# pertamina.net
KiCad netlist of a schematic drawn in EAGLE
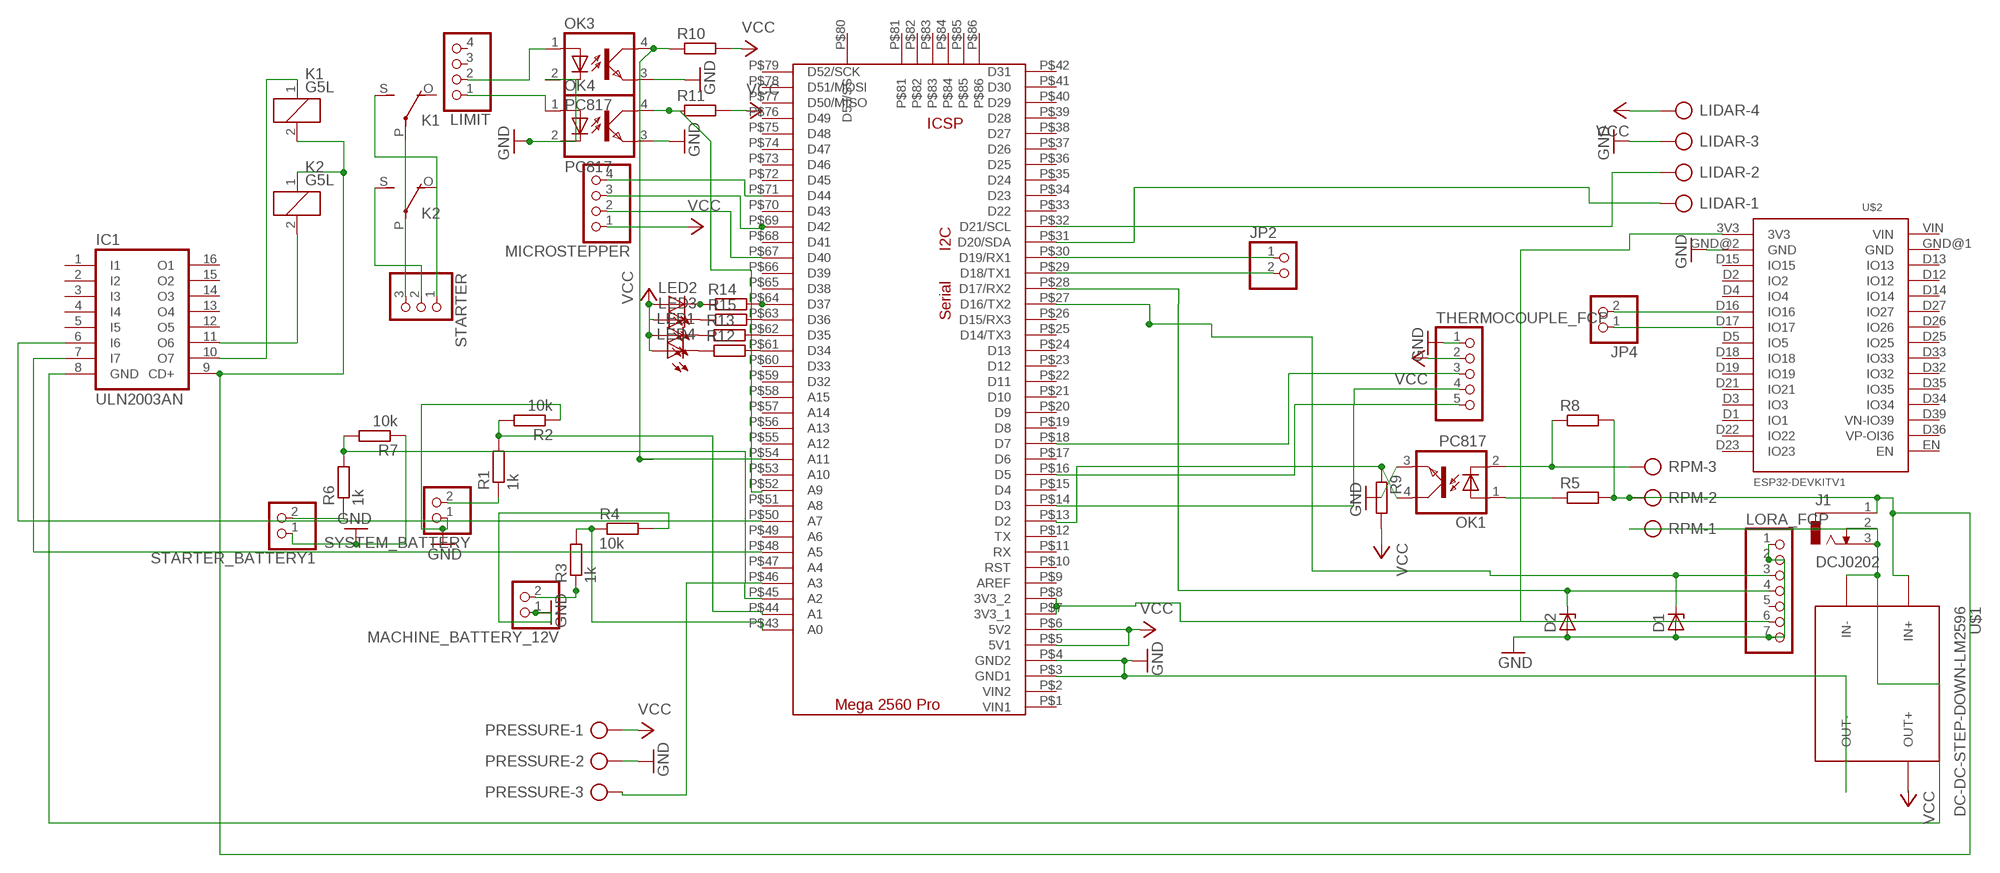
[diagram p0: schematic, sheet 1]

(export (version "E")
  (design (tool "Eeschema 10.0.6"))
  (components
    (comp (ref "D1")
      (value "ZENER-DIODEDO35Z10")
      (footprint "eagle-import:DO35Z10")
      (libsource (lib "eagle-import") (part "ZENER-DIODEDO35Z10"))
    )
    (comp (ref "D2")
      (value "ZENER-DIODEDO35Z10")
      (footprint "eagle-import:DO35Z10")
      (libsource (lib "eagle-import") (part "ZENER-DIODEDO35Z10"))
    )
    (comp (ref "IC1")
      (value "ULN2003AN")
      (footprint "eagle-import:DIL16")
      (libsource (lib "eagle-import") (part "ULN2003AN"))
    )
    (comp (ref "J1")
      (value "DCJ0202")
      (footprint "eagle-import:DCJ0202")
      (libsource (lib "eagle-import") (part "DCJ0202"))
    )
    (comp (ref "JP2")
      (value "PINHD-1X2")
      (footprint "eagle-import:1X02")
      (libsource (lib "eagle-import") (part "PINHD-1X2"))
    )
    (comp (ref "JP4")
      (value "PINHD-1X2")
      (footprint "eagle-import:1X02")
      (libsource (lib "eagle-import") (part "PINHD-1X2"))
    )
    (comp (ref "K1")
      (value "G5L")
      (footprint "eagle-import:G5LE")
      (libsource (lib "eagle-import") (part "G5L"))
    )
    (comp (ref "K2")
      (value "G5L")
      (footprint "eagle-import:G5LE")
      (libsource (lib "eagle-import") (part "G5L"))
    )
    (comp (ref "LED1")
      (value "LED5MM")
      (footprint "eagle-import:LED5MM")
      (libsource (lib "eagle-import") (part "LED5MM"))
    )
    (comp (ref "LED2")
      (value "LED5MM")
      (footprint "eagle-import:LED5MM")
      (libsource (lib "eagle-import") (part "LED5MM"))
    )
    (comp (ref "LED3")
      (value "LED5MM")
      (footprint "eagle-import:LED5MM")
      (libsource (lib "eagle-import") (part "LED5MM"))
    )
    (comp (ref "LED4")
      (value "LED5MM")
      (footprint "eagle-import:LED5MM")
      (libsource (lib "eagle-import") (part "LED5MM"))
    )
    (comp (ref "LIDAR")
      (value "AK300/4")
      (footprint "eagle-import:AK300_4")
      (libsource (lib "eagle-import") (part "AK300/4"))
    )
    (comp (ref "LIMIT")
      (value "PINHD-1X4")
      (footprint "eagle-import:1X04")
      (libsource (lib "eagle-import") (part "PINHD-1X4"))
    )
    (comp (ref "LORA_FCP")
      (value "PINHD-1X7")
      (footprint "eagle-import:1X07")
      (libsource (lib "eagle-import") (part "PINHD-1X7"))
    )
    (comp (ref "MACHINE_BATTERY_12V")
      (value "PINHD-1X2")
      (footprint "eagle-import:1X02")
      (libsource (lib "eagle-import") (part "PINHD-1X2"))
    )
    (comp (ref "MICROSTEPPER")
      (value "PINHD-1X4")
      (footprint "eagle-import:1X04")
      (libsource (lib "eagle-import") (part "PINHD-1X4"))
    )
    (comp (ref "OK1")
      (value "PC817")
      (footprint "eagle-import:DIL04")
      (fields (field (name "MPN") "PC817X4J000F"))
      (libsource (lib "eagle-import") (part "PC817"))
    )
    (comp (ref "OK3")
      (value "PC817")
      (footprint "eagle-import:DIL04")
      (fields (field (name "MPN") "PC817X4J000F"))
      (libsource (lib "eagle-import") (part "PC817"))
    )
    (comp (ref "OK4")
      (value "PC817")
      (footprint "eagle-import:DIL04")
      (fields (field (name "MPN") "PC817X4J000F"))
      (libsource (lib "eagle-import") (part "PC817"))
    )
    (comp (ref "PRESSURE")
      (value "AK300/3")
      (footprint "eagle-import:AK300_3")
      (libsource (lib "eagle-import") (part "AK300/3"))
    )
    (comp (ref "R1")
      (value "1k")
      (footprint "eagle-import:0204_7")
      (libsource (lib "eagle-import") (part "R-EU_0204/7"))
    )
    (comp (ref "R2")
      (value "10k")
      (footprint "eagle-import:0204_7")
      (libsource (lib "eagle-import") (part "R-EU_0204/7"))
    )
    (comp (ref "R3")
      (value "1k")
      (footprint "eagle-import:0204_7")
      (libsource (lib "eagle-import") (part "R-EU_0204/7"))
    )
    (comp (ref "R4")
      (value "10k")
      (footprint "eagle-import:0204_7")
      (libsource (lib "eagle-import") (part "R-EU_0204/7"))
    )
    (comp (ref "R5")
      (value "R-EU_0204/7")
      (footprint "eagle-import:0204_7")
      (libsource (lib "eagle-import") (part "R-EU_0204/7"))
    )
    (comp (ref "R6")
      (value "1k")
      (footprint "eagle-import:0204_7")
      (libsource (lib "eagle-import") (part "R-EU_0204/7"))
    )
    (comp (ref "R7")
      (value "10k")
      (footprint "eagle-import:0204_7")
      (libsource (lib "eagle-import") (part "R-EU_0204/7"))
    )
    (comp (ref "R8")
      (value "R-EU_0204/7")
      (footprint "eagle-import:0204_7")
      (libsource (lib "eagle-import") (part "R-EU_0204/7"))
    )
    (comp (ref "R9")
      (value "R-EU_0204/7")
      (footprint "eagle-import:0204_7")
      (libsource (lib "eagle-import") (part "R-EU_0204/7"))
    )
    (comp (ref "R10")
      (value "R-EU_0204/7")
      (footprint "eagle-import:0204_7")
      (libsource (lib "eagle-import") (part "R-EU_0204/7"))
    )
    (comp (ref "R11")
      (value "R-EU_0204/7")
      (footprint "eagle-import:0204_7")
      (libsource (lib "eagle-import") (part "R-EU_0204/7"))
    )
    (comp (ref "R12")
      (value "R-EU_0204/7")
      (footprint "eagle-import:0204_7")
      (libsource (lib "eagle-import") (part "resistor_R-EU_0204/7"))
    )
    (comp (ref "R13")
      (value "R-EU_0204/7")
      (footprint "eagle-import:0204_7")
      (libsource (lib "eagle-import") (part "resistor_R-EU_0204/7"))
    )
    (comp (ref "R14")
      (value "R-EU_0204/7")
      (footprint "eagle-import:0204_7")
      (libsource (lib "eagle-import") (part "resistor_R-EU_0204/7"))
    )
    (comp (ref "R15")
      (value "R-EU_0204/7")
      (footprint "eagle-import:0204_7")
      (libsource (lib "eagle-import") (part "resistor_R-EU_0204/7"))
    )
    (comp (ref "RPM")
      (value "AK300/3")
      (footprint "eagle-import:AK300_3")
      (libsource (lib "eagle-import") (part "AK300/3"))
    )
    (comp (ref "STARTER")
      (value "PINHD-1X3")
      (footprint "eagle-import:1X03")
      (libsource (lib "eagle-import") (part "PINHD-1X3"))
    )
    (comp (ref "STARTER_BATTERY1")
      (value "PINHD-1X2")
      (footprint "eagle-import:1X02")
      (libsource (lib "eagle-import") (part "PINHD-1X2"))
    )
    (comp (ref "SYSTEM_BATTERY")
      (value "PINHD-1X2")
      (footprint "eagle-import:1X02")
      (libsource (lib "eagle-import") (part "PINHD-1X2"))
    )
    (comp (ref "THERMOCOUPLE_FCP")
      (value "PINHD-1X5")
      (footprint "eagle-import:1X05")
      (libsource (lib "eagle-import") (part "PINHD-1X5"))
    )
    (comp (ref "U$1")
      (value "DC-DC-STEP-DOWN-LM2596")
      (footprint "eagle-import:DC-DC-STEP-DOWN-LM2596")
      (libsource (lib "eagle-import") (part "DC-DC-STEP-DOWN-LM2596"))
    )
    (comp (ref "U$2")
      (value "ESP32DEVKITV1")
      (footprint "eagle-import:ESP32-DEVKITV1")
      (libsource (lib "eagle-import") (part "ESP32DEVKITV1"))
    )
    (comp (ref "U$3")
      (value "MEGAPROMINI")
      (footprint "eagle-import:MEGAPROMINI")
      (libsource (lib "eagle-import") (part "MEGAPROMINI"))
    )
  )
  (nets
    (net (code "1") (name "GND") (class "Default")
      (node (ref "D1") (pin "A") (pinfunction "A_A") (pintype "passive"))
      (node (ref "D2") (pin "A") (pinfunction "A_A") (pintype "passive"))
      (node (ref "LIDAR") (pin "3") (pinfunction "KL_3") (pintype "passive"))
      (node (ref "LORA_FCP") (pin "1") (pinfunction "1_1") (pintype "passive"))
      (node (ref "LORA_FCP") (pin "2") (pinfunction "2_2") (pintype "passive"))
      (node (ref "LORA_FCP") (pin "7") (pinfunction "7_7") (pintype "passive"))
      (node (ref "MACHINE_BATTERY_12V") (pin "1") (pinfunction "1_1") (pintype "passive"))
      (node (ref "OK1") (pin "3") (pinfunction "EMIT_3") (pintype "passive"))
      (node (ref "OK3") (pin "2") (pinfunction "C_2") (pintype "passive"))
      (node (ref "OK3") (pin "3") (pinfunction "EMIT_3") (pintype "passive"))
      (node (ref "OK4") (pin "2") (pinfunction "C_2") (pintype "passive"))
      (node (ref "OK4") (pin "3") (pinfunction "EMIT_3") (pintype "passive"))
      (node (ref "PRESSURE") (pin "2") (pinfunction "KL_2") (pintype "passive"))
      (node (ref "R2") (pin "1") (pinfunction "1_1") (pintype "passive"))
      (node (ref "R4") (pin "2") (pinfunction "2_2") (pintype "passive"))
      (node (ref "R7") (pin "1") (pinfunction "1_1") (pintype "passive"))
      (node (ref "STARTER_BATTERY1") (pin "1") (pinfunction "1_1") (pintype "passive"))
      (node (ref "SYSTEM_BATTERY") (pin "1") (pinfunction "1_1") (pintype "passive"))
      (node (ref "THERMOCOUPLE_FCP") (pin "1") (pinfunction "1_1") (pintype "passive"))
      (node (ref "U$1") (pin "OUT-") (pinfunction "OUT-_OUT-") (pintype "bidirectional"))
      (node (ref "U$2") (pin "GND@2") (pinfunction "GND_GND@2") (pintype "bidirectional"))
      (node (ref "U$3") (pin "P$3") (pinfunction "GND1_P$3") (pintype "bidirectional"))
      (node (ref "U$3") (pin "P$4") (pinfunction "GND2_P$4") (pintype "bidirectional"))
    )
    (net (code "2") (name "Net-(IC1-CD+)") (class "Default")
      (node (ref "IC1") (pin "9") (pinfunction "CD+_9") (pintype "passive"))
      (node (ref "J1") (pin "1") (pinfunction "1_1") (pintype "passive"))
      (node (ref "K1") (pin "2") (pinfunction "2_2") (pintype "passive"))
      (node (ref "K2") (pin "1") (pinfunction "1_1") (pintype "passive"))
      (node (ref "R5") (pin "2") (pinfunction "2_2") (pintype "passive"))
      (node (ref "R8") (pin "2") (pinfunction "2_2") (pintype "passive"))
      (node (ref "RPM") (pin "2") (pinfunction "KL_2") (pintype "passive"))
      (node (ref "U$1") (pin "IN+") (pinfunction "IN+_IN+") (pintype "bidirectional"))
    )
    (net (code "3") (name "Net-(IC1-GND)") (class "Default")
      (node (ref "IC1") (pin "8") (pinfunction "GND_8") (pintype "power_in"))
      (node (ref "J1") (pin "2") (pinfunction "2_2") (pintype "passive"))
      (node (ref "J1") (pin "3") (pinfunction "3_3") (pintype "passive"))
      (node (ref "RPM") (pin "1") (pinfunction "KL_1") (pintype "passive"))
      (node (ref "U$1") (pin "IN-") (pinfunction "IN-_IN-") (pintype "bidirectional"))
    )
    (net (code "4") (name "Net-(IC1-I6)") (class "Default")
      (node (ref "IC1") (pin "6") (pinfunction "I6_6") (pintype "input"))
      (node (ref "U$3") (pin "P$50") (pinfunction "A7_P$50") (pintype "bidirectional"))
    )
    (net (code "5") (name "Net-(IC1-I7)") (class "Default")
      (node (ref "IC1") (pin "7") (pinfunction "I7_7") (pintype "input"))
      (node (ref "U$3") (pin "P$48") (pinfunction "A5_P$48") (pintype "bidirectional"))
    )
    (net (code "6") (name "Net-(IC1-O6)") (class "Default")
      (node (ref "IC1") (pin "11") (pinfunction "O6_11") (pintype "open_collector"))
      (node (ref "K2") (pin "2") (pinfunction "2_2") (pintype "passive"))
    )
    (net (code "7") (name "Net-(IC1-O7)") (class "Default")
      (node (ref "IC1") (pin "10") (pinfunction "O7_10") (pintype "open_collector"))
      (node (ref "K1") (pin "1") (pinfunction "1_1") (pintype "passive"))
    )
    (net (code "8") (name "Net-(K1-PadP)") (class "Default")
      (node (ref "K1") (pin "P") (pinfunction "P_P") (pintype "passive"))
      (node (ref "K2") (pin "P") (pinfunction "P_P") (pintype "passive"))
      (node (ref "STARTER") (pin "3") (pinfunction "3_3") (pintype "passive"))
    )
    (net (code "9") (name "Net-(K1-PadS)") (class "Default")
      (node (ref "K1") (pin "S") (pinfunction "S_S") (pintype "passive"))
      (node (ref "STARTER") (pin "1") (pinfunction "1_1") (pintype "passive"))
    )
    (net (code "10") (name "Net-(K2-PadS)") (class "Default")
      (node (ref "K2") (pin "S") (pinfunction "S_S") (pintype "passive"))
      (node (ref "STARTER") (pin "2") (pinfunction "2_2") (pintype "passive"))
    )
    (net (code "11") (name "Net-(LED1-C)") (class "Default")
      (node (ref "LED1") (pin "K") (pinfunction "C_K") (pintype "passive"))
      (node (ref "R13") (pin "1") (pinfunction "1_1") (pintype "passive"))
    )
    (net (code "12") (name "Net-(LED2-C)") (class "Default")
      (node (ref "LED2") (pin "K") (pinfunction "C_K") (pintype "passive"))
      (node (ref "R14") (pin "1") (pinfunction "1_1") (pintype "passive"))
    )
    (net (code "13") (name "Net-(LED3-C)") (class "Default")
      (node (ref "LED3") (pin "K") (pinfunction "C_K") (pintype "passive"))
      (node (ref "R15") (pin "1") (pinfunction "1_1") (pintype "passive"))
    )
    (net (code "14") (name "Net-(LED4-C)") (class "Default")
      (node (ref "LED4") (pin "K") (pinfunction "C_K") (pintype "passive"))
      (node (ref "R12") (pin "1") (pinfunction "1_1") (pintype "passive"))
    )
    (net (code "15") (name "Net-(LIDARA-KL)") (class "Default")
      (node (ref "LIDAR") (pin "1") (pinfunction "KL_1") (pintype "passive"))
      (node (ref "U$3") (pin "P$31") (pinfunction "D20/SDA_P$31") (pintype "bidirectional"))
    )
    (net (code "16") (name "Net-(LIDARB-KL)") (class "Default")
      (node (ref "LIDAR") (pin "2") (pinfunction "KL_2") (pintype "passive"))
      (node (ref "U$3") (pin "P$32") (pinfunction "D21/SCL_P$32") (pintype "bidirectional"))
    )
    (net (code "17") (name "Net-(MACHINE_BATTERY_12V-Pad2)") (class "Default")
      (node (ref "MACHINE_BATTERY_12V") (pin "2") (pinfunction "2_2") (pintype "passive"))
      (node (ref "R3") (pin "1") (pinfunction "1_1") (pintype "passive"))
    )
    (net (code "18") (name "Net-(OK1-A)") (class "Default")
      (node (ref "OK1") (pin "1") (pinfunction "A_1") (pintype "passive"))
      (node (ref "R5") (pin "1") (pinfunction "1_1") (pintype "passive"))
    )
    (net (code "19") (name "Net-(OK1-C)") (class "Default")
      (node (ref "OK1") (pin "2") (pinfunction "C_2") (pintype "passive"))
      (node (ref "R8") (pin "1") (pinfunction "1_1") (pintype "passive"))
      (node (ref "RPM") (pin "3") (pinfunction "KL_3") (pintype "passive"))
    )
    (net (code "20") (name "Net-(OK1-COL)") (class "Default")
      (node (ref "OK1") (pin "4") (pinfunction "COL_4") (pintype "passive"))
      (node (ref "R9") (pin "1") (pinfunction "1_1") (pintype "passive"))
      (node (ref "U$3") (pin "P$13") (pinfunction "D2_P$13") (pintype "bidirectional"))
    )
    (net (code "21") (name "Net-(OK3-A)") (class "Default")
      (node (ref "LIMIT") (pin "2") (pinfunction "2_2") (pintype "passive"))
      (node (ref "OK3") (pin "1") (pinfunction "A_1") (pintype "passive"))
    )
    (net (code "22") (name "Net-(OK3-COL)") (class "Default")
      (node (ref "OK3") (pin "4") (pinfunction "COL_4") (pintype "passive"))
      (node (ref "R10") (pin "1") (pinfunction "1_1") (pintype "passive"))
      (node (ref "U$3") (pin "P$54") (pinfunction "A11_P$54") (pintype "bidirectional"))
    )
    (net (code "23") (name "Net-(OK4-A)") (class "Default")
      (node (ref "LIMIT") (pin "1") (pinfunction "1_1") (pintype "passive"))
      (node (ref "OK4") (pin "1") (pinfunction "A_1") (pintype "passive"))
    )
    (net (code "24") (name "Net-(OK4-COL)") (class "Default")
      (node (ref "OK4") (pin "4") (pinfunction "COL_4") (pintype "passive"))
      (node (ref "R11") (pin "1") (pinfunction "1_1") (pintype "passive"))
      (node (ref "U$3") (pin "P$52") (pinfunction "A9_P$52") (pintype "bidirectional"))
    )
    (net (code "25") (name "Net-(PRESSUREC-KL)") (class "Default")
      (node (ref "PRESSURE") (pin "3") (pinfunction "KL_3") (pintype "passive"))
      (node (ref "U$3") (pin "P$46") (pinfunction "A3_P$46") (pintype "bidirectional"))
    )
    (net (code "26") (name "Net-(R1-Pad1)") (class "Default")
      (node (ref "R1") (pin "1") (pinfunction "1_1") (pintype "passive"))
      (node (ref "SYSTEM_BATTERY") (pin "2") (pinfunction "2_2") (pintype "passive"))
    )
    (net (code "27") (name "Net-(R6-Pad1)") (class "Default")
      (node (ref "R6") (pin "1") (pinfunction "1_1") (pintype "passive"))
      (node (ref "STARTER_BATTERY1") (pin "2") (pinfunction "2_2") (pintype "passive"))
    )
    (net (code "28") (name "Net-(U$2-IO16)") (class "Default")
      (node (ref "JP4") (pin "2") (pinfunction "2_2") (pintype "passive"))
      (node (ref "U$2") (pin "D16") (pinfunction "IO16_D16") (pintype "bidirectional"))
    )
    (net (code "29") (name "Net-(U$2-IO17)") (class "Default")
      (node (ref "JP4") (pin "1") (pinfunction "1_1") (pintype "passive"))
      (node (ref "U$2") (pin "D17") (pinfunction "IO17_D17") (pintype "bidirectional"))
    )
    (net (code "30") (name "Net-(U$3-3V3_1)") (class "Default")
      (node (ref "LORA_FCP") (pin "6") (pinfunction "6_6") (pintype "passive"))
      (node (ref "U$2") (pin "3V3") (pinfunction "3V3_3V3") (pintype "bidirectional"))
      (node (ref "U$3") (pin "P$7") (pinfunction "3V3_1_P$7") (pintype "bidirectional"))
      (node (ref "U$3") (pin "P$8") (pinfunction "3V3_2_P$8") (pintype "bidirectional"))
    )
    (net (code "31") (name "Net-(U$3-A0)") (class "Default")
      (node (ref "R3") (pin "2") (pinfunction "2_2") (pintype "passive"))
      (node (ref "R4") (pin "1") (pinfunction "1_1") (pintype "passive"))
      (node (ref "U$3") (pin "P$43") (pinfunction "A0_P$43") (pintype "bidirectional"))
    )
    (net (code "32") (name "Net-(U$3-A1)") (class "Default")
      (node (ref "R1") (pin "2") (pinfunction "2_2") (pintype "passive"))
      (node (ref "R2") (pin "2") (pinfunction "2_2") (pintype "passive"))
      (node (ref "U$3") (pin "P$44") (pinfunction "A1_P$44") (pintype "bidirectional"))
    )
    (net (code "33") (name "Net-(U$3-A2)") (class "Default")
      (node (ref "R6") (pin "2") (pinfunction "2_2") (pintype "passive"))
      (node (ref "R7") (pin "2") (pinfunction "2_2") (pintype "passive"))
      (node (ref "U$3") (pin "P$45") (pinfunction "A2_P$45") (pintype "bidirectional"))
    )
    (net (code "34") (name "Net-(U$3-D3)") (class "Default")
      (node (ref "THERMOCOUPLE_FCP") (pin "4") (pinfunction "4_4") (pintype "passive"))
      (node (ref "U$3") (pin "P$14") (pinfunction "D3_P$14") (pintype "bidirectional"))
    )
    (net (code "35") (name "Net-(U$3-D5)") (class "Default")
      (node (ref "THERMOCOUPLE_FCP") (pin "5") (pinfunction "5_5") (pintype "passive"))
      (node (ref "U$3") (pin "P$16") (pinfunction "D5_P$16") (pintype "bidirectional"))
    )
    (net (code "36") (name "Net-(U$3-D7)") (class "Default")
      (node (ref "THERMOCOUPLE_FCP") (pin "3") (pinfunction "3_3") (pintype "passive"))
      (node (ref "U$3") (pin "P$18") (pinfunction "D7_P$18") (pintype "bidirectional"))
    )
    (net (code "37") (name "Net-(U$3-D16{slash}TX2)") (class "Default")
      (node (ref "D1") (pin "C") (pinfunction "C_C") (pintype "passive"))
      (node (ref "LORA_FCP") (pin "3") (pinfunction "3_3") (pintype "passive"))
      (node (ref "U$3") (pin "P$27") (pinfunction "D16/TX2_P$27") (pintype "bidirectional"))
    )
    (net (code "38") (name "Net-(U$3-D17{slash}RX2)") (class "Default")
      (node (ref "D2") (pin "C") (pinfunction "C_C") (pintype "passive"))
      (node (ref "LORA_FCP") (pin "4") (pinfunction "4_4") (pintype "passive"))
      (node (ref "U$3") (pin "P$28") (pinfunction "D17/RX2_P$28") (pintype "bidirectional"))
    )
    (net (code "39") (name "Net-(U$3-D18{slash}TX1)") (class "Default")
      (node (ref "JP2") (pin "2") (pinfunction "2_2") (pintype "passive"))
      (node (ref "U$3") (pin "P$29") (pinfunction "D18/TX1_P$29") (pintype "bidirectional"))
    )
    (net (code "40") (name "Net-(U$3-D19{slash}RX1)") (class "Default")
      (node (ref "JP2") (pin "1") (pinfunction "1_1") (pintype "passive"))
      (node (ref "U$3") (pin "P$30") (pinfunction "D19/RX1_P$30") (pintype "bidirectional"))
    )
    (net (code "41") (name "Net-(U$3-D34)") (class "Default")
      (node (ref "R12") (pin "2") (pinfunction "2_2") (pintype "passive"))
      (node (ref "U$3") (pin "P$61") (pinfunction "D34_P$61") (pintype "bidirectional"))
    )
    (net (code "42") (name "Net-(U$3-D35)") (class "Default")
      (node (ref "R13") (pin "2") (pinfunction "2_2") (pintype "passive"))
      (node (ref "U$3") (pin "P$62") (pinfunction "D35_P$62") (pintype "bidirectional"))
    )
    (net (code "43") (name "Net-(U$3-D36)") (class "Default")
      (node (ref "R15") (pin "2") (pinfunction "2_2") (pintype "passive"))
      (node (ref "U$3") (pin "P$63") (pinfunction "D36_P$63") (pintype "bidirectional"))
    )
    (net (code "44") (name "Net-(U$3-D37)") (class "Default")
      (node (ref "R14") (pin "2") (pinfunction "2_2") (pintype "passive"))
      (node (ref "U$3") (pin "P$64") (pinfunction "D37_P$64") (pintype "bidirectional"))
    )
    (net (code "45") (name "Net-(U$3-D40)") (class "Default")
      (node (ref "MICROSTEPPER") (pin "2") (pinfunction "2_2") (pintype "passive"))
      (node (ref "U$3") (pin "P$67") (pinfunction "D40_P$67") (pintype "bidirectional"))
    )
    (net (code "46") (name "Net-(U$3-D42)") (class "Default")
      (node (ref "MICROSTEPPER") (pin "3") (pinfunction "3_3") (pintype "passive"))
      (node (ref "U$3") (pin "P$69") (pinfunction "D42_P$69") (pintype "bidirectional"))
    )
    (net (code "47") (name "Net-(U$3-D44)") (class "Default")
      (node (ref "MICROSTEPPER") (pin "4") (pinfunction "4_4") (pintype "passive"))
      (node (ref "U$3") (pin "P$71") (pinfunction "D44_P$71") (pintype "bidirectional"))
    )
    (net (code "48") (name "VCC") (class "Default")
      (node (ref "LED1") (pin "A") (pinfunction "A_A") (pintype "passive"))
      (node (ref "LED2") (pin "A") (pinfunction "A_A") (pintype "passive"))
      (node (ref "LED3") (pin "A") (pinfunction "A_A") (pintype "passive"))
      (node (ref "LED4") (pin "A") (pinfunction "A_A") (pintype "passive"))
      (node (ref "LIDAR") (pin "4") (pinfunction "KL_4") (pintype "passive"))
      (node (ref "MICROSTEPPER") (pin "1") (pinfunction "1_1") (pintype "passive"))
      (node (ref "PRESSURE") (pin "1") (pinfunction "KL_1") (pintype "passive"))
      (node (ref "R10") (pin "2") (pinfunction "2_2") (pintype "passive"))
      (node (ref "R11") (pin "2") (pinfunction "2_2") (pintype "passive"))
      (node (ref "R9") (pin "2") (pinfunction "2_2") (pintype "passive"))
      (node (ref "THERMOCOUPLE_FCP") (pin "2") (pinfunction "2_2") (pintype "passive"))
      (node (ref "U$1") (pin "OUT+") (pinfunction "OUT+_OUT+") (pintype "bidirectional"))
      (node (ref "U$3") (pin "P$5") (pinfunction "5V1_P$5") (pintype "bidirectional"))
      (node (ref "U$3") (pin "P$6") (pinfunction "5V2_P$6") (pintype "bidirectional"))
    )
    (net (code "49") (name "unconnected-(IC1-I1-Pad1)") (class "Default")
      (node (ref "IC1") (pin "1") (pinfunction "I1_1") (pintype "input"))
    )
    (net (code "50") (name "unconnected-(IC1-I2-Pad2)") (class "Default")
      (node (ref "IC1") (pin "2") (pinfunction "I2_2") (pintype "input"))
    )
    (net (code "51") (name "unconnected-(IC1-I3-Pad3)") (class "Default")
      (node (ref "IC1") (pin "3") (pinfunction "I3_3") (pintype "input"))
    )
    (net (code "52") (name "unconnected-(IC1-I4-Pad4)") (class "Default")
      (node (ref "IC1") (pin "4") (pinfunction "I4_4") (pintype "input"))
    )
    (net (code "53") (name "unconnected-(IC1-I5-Pad5)") (class "Default")
      (node (ref "IC1") (pin "5") (pinfunction "I5_5") (pintype "input"))
    )
    (net (code "54") (name "unconnected-(IC1-O1-Pad16)") (class "Default")
      (node (ref "IC1") (pin "16") (pinfunction "O1_16") (pintype "open_collector"))
    )
    (net (code "55") (name "unconnected-(IC1-O2-Pad15)") (class "Default")
      (node (ref "IC1") (pin "15") (pinfunction "O2_15") (pintype "open_collector"))
    )
    (net (code "56") (name "unconnected-(IC1-O3-Pad14)") (class "Default")
      (node (ref "IC1") (pin "14") (pinfunction "O3_14") (pintype "open_collector"))
    )
    (net (code "57") (name "unconnected-(IC1-O4-Pad13)") (class "Default")
      (node (ref "IC1") (pin "13") (pinfunction "O4_13") (pintype "open_collector"))
    )
    (net (code "58") (name "unconnected-(IC1-O5-Pad12)") (class "Default")
      (node (ref "IC1") (pin "12") (pinfunction "O5_12") (pintype "open_collector"))
    )
    (net (code "59") (name "unconnected-(K1-PadO)") (class "Default")
      (node (ref "K1") (pin "O") (pinfunction "O_O") (pintype "passive"))
    )
    (net (code "60") (name "unconnected-(K2-PadO)") (class "Default")
      (node (ref "K2") (pin "O") (pinfunction "O_O") (pintype "passive"))
    )
    (net (code "61") (name "unconnected-(LIMIT-Pad3)") (class "Default")
      (node (ref "LIMIT") (pin "3") (pinfunction "3_3") (pintype "passive"))
    )
    (net (code "62") (name "unconnected-(LIMIT-Pad4)") (class "Default")
      (node (ref "LIMIT") (pin "4") (pinfunction "4_4") (pintype "passive"))
    )
    (net (code "63") (name "unconnected-(LORA_FCP-Pad5)") (class "Default")
      (node (ref "LORA_FCP") (pin "5") (pinfunction "5_5") (pintype "passive"))
    )
    (net (code "64") (name "unconnected-(U$2-GND-PadGND@1)") (class "Default")
      (node (ref "U$2") (pin "GND@1") (pinfunction "GND_GND@1") (pintype "bidirectional"))
    )
    (net (code "65") (name "unconnected-(U$2-IO1-PadD1)") (class "Default")
      (node (ref "U$2") (pin "D1") (pinfunction "IO1_D1") (pintype "bidirectional"))
    )
    (net (code "66") (name "unconnected-(U$2-IO2-PadD2)") (class "Default")
      (node (ref "U$2") (pin "D2") (pinfunction "IO2_D2") (pintype "bidirectional"))
    )
    (net (code "67") (name "unconnected-(U$2-IO3-PadD3)") (class "Default")
      (node (ref "U$2") (pin "D3") (pinfunction "IO3_D3") (pintype "bidirectional"))
    )
    (net (code "68") (name "unconnected-(U$2-IO4-PadD4)") (class "Default")
      (node (ref "U$2") (pin "D4") (pinfunction "IO4_D4") (pintype "bidirectional"))
    )
    (net (code "69") (name "unconnected-(U$2-IO5-PadD5)") (class "Default")
      (node (ref "U$2") (pin "D5") (pinfunction "IO5_D5") (pintype "bidirectional"))
    )
    (net (code "70") (name "unconnected-(U$2-IO12-PadD12)") (class "Default")
      (node (ref "U$2") (pin "D12") (pinfunction "IO12_D12") (pintype "bidirectional"))
    )
    (net (code "71") (name "unconnected-(U$2-IO13-PadD13)") (class "Default")
      (node (ref "U$2") (pin "D13") (pinfunction "IO13_D13") (pintype "bidirectional"))
    )
    (net (code "72") (name "unconnected-(U$2-IO14-PadD14)") (class "Default")
      (node (ref "U$2") (pin "D14") (pinfunction "IO14_D14") (pintype "bidirectional"))
    )
    (net (code "73") (name "unconnected-(U$2-IO15-PadD15)") (class "Default")
      (node (ref "U$2") (pin "D15") (pinfunction "IO15_D15") (pintype "bidirectional"))
    )
    (net (code "74") (name "unconnected-(U$2-IO18-PadD18)") (class "Default")
      (node (ref "U$2") (pin "D18") (pinfunction "IO18_D18") (pintype "bidirectional"))
    )
    (net (code "75") (name "unconnected-(U$2-IO19-PadD19)") (class "Default")
      (node (ref "U$2") (pin "D19") (pinfunction "IO19_D19") (pintype "bidirectional"))
    )
    (net (code "76") (name "unconnected-(U$2-IO21-PadD21)") (class "Default")
      (node (ref "U$2") (pin "D21") (pinfunction "IO21_D21") (pintype "bidirectional"))
    )
    (net (code "77") (name "unconnected-(U$2-IO22-PadD22)") (class "Default")
      (node (ref "U$2") (pin "D22") (pinfunction "IO22_D22") (pintype "bidirectional"))
    )
    (net (code "78") (name "unconnected-(U$2-IO23-PadD23)") (class "Default")
      (node (ref "U$2") (pin "D23") (pinfunction "IO23_D23") (pintype "bidirectional"))
    )
    (net (code "79") (name "unconnected-(U$2-IO25-PadD25)") (class "Default")
      (node (ref "U$2") (pin "D25") (pinfunction "IO25_D25") (pintype "bidirectional"))
    )
    (net (code "80") (name "unconnected-(U$2-IO26-PadD26)") (class "Default")
      (node (ref "U$2") (pin "D26") (pinfunction "IO26_D26") (pintype "bidirectional"))
    )
    (net (code "81") (name "unconnected-(U$2-IO27-PadD27)") (class "Default")
      (node (ref "U$2") (pin "D27") (pinfunction "IO27_D27") (pintype "bidirectional"))
    )
    (net (code "82") (name "unconnected-(U$2-IO32-PadD32)") (class "Default")
      (node (ref "U$2") (pin "D32") (pinfunction "IO32_D32") (pintype "bidirectional"))
    )
    (net (code "83") (name "unconnected-(U$2-IO33-PadD33)") (class "Default")
      (node (ref "U$2") (pin "D33") (pinfunction "IO33_D33") (pintype "bidirectional"))
    )
    (net (code "84") (name "unconnected-(U$2-IO34-PadD34)") (class "Default")
      (node (ref "U$2") (pin "D34") (pinfunction "IO34_D34") (pintype "bidirectional"))
    )
    (net (code "85") (name "unconnected-(U$2-IO35-PadD35)") (class "Default")
      (node (ref "U$2") (pin "D35") (pinfunction "IO35_D35") (pintype "bidirectional"))
    )
    (net (code "86") (name "unconnected-(U$2-PadEN)") (class "Default")
      (node (ref "U$2") (pin "EN") (pinfunction "EN_EN") (pintype "bidirectional"))
    )
    (net (code "87") (name "unconnected-(U$2-PadVIN)") (class "Default")
      (node (ref "U$2") (pin "VIN") (pinfunction "VIN_VIN") (pintype "bidirectional"))
    )
    (net (code "88") (name "unconnected-(U$2-VN-IO39-PadD39)") (class "Default")
      (node (ref "U$2") (pin "D39") (pinfunction "VN-IO39_D39") (pintype "bidirectional"))
    )
    (net (code "89") (name "unconnected-(U$2-VP-OI36-PadD36)") (class "Default")
      (node (ref "U$2") (pin "D36") (pinfunction "VP-OI36_D36") (pintype "bidirectional"))
    )
    (net (code "90") (name "unconnected-(U$3-A4-PadP$47)") (class "Default")
      (node (ref "U$3") (pin "P$47") (pinfunction "A4_P$47") (pintype "bidirectional"))
    )
    (net (code "91") (name "unconnected-(U$3-A6-PadP$49)") (class "Default")
      (node (ref "U$3") (pin "P$49") (pinfunction "A6_P$49") (pintype "bidirectional"))
    )
    (net (code "92") (name "unconnected-(U$3-A8-PadP$51)") (class "Default")
      (node (ref "U$3") (pin "P$51") (pinfunction "A8_P$51") (pintype "bidirectional"))
    )
    (net (code "93") (name "unconnected-(U$3-A10-PadP$53)") (class "Default")
      (node (ref "U$3") (pin "P$53") (pinfunction "A10_P$53") (pintype "bidirectional"))
    )
    (net (code "94") (name "unconnected-(U$3-A12-PadP$55)") (class "Default")
      (node (ref "U$3") (pin "P$55") (pinfunction "A12_P$55") (pintype "bidirectional"))
    )
    (net (code "95") (name "unconnected-(U$3-A13-PadP$56)") (class "Default")
      (node (ref "U$3") (pin "P$56") (pinfunction "A13_P$56") (pintype "bidirectional"))
    )
    (net (code "96") (name "unconnected-(U$3-A14-PadP$57)") (class "Default")
      (node (ref "U$3") (pin "P$57") (pinfunction "A14_P$57") (pintype "bidirectional"))
    )
    (net (code "97") (name "unconnected-(U$3-A15-PadP$58)") (class "Default")
      (node (ref "U$3") (pin "P$58") (pinfunction "A15_P$58") (pintype "bidirectional"))
    )
    (net (code "98") (name "unconnected-(U$3-AREF-PadP$9)") (class "Default")
      (node (ref "U$3") (pin "P$9") (pinfunction "AREF_P$9") (pintype "bidirectional"))
    )
    (net (code "99") (name "unconnected-(U$3-D4-PadP$15)") (class "Default")
      (node (ref "U$3") (pin "P$15") (pinfunction "D4_P$15") (pintype "bidirectional"))
    )
    (net (code "100") (name "unconnected-(U$3-D6-PadP$17)") (class "Default")
      (node (ref "U$3") (pin "P$17") (pinfunction "D6_P$17") (pintype "bidirectional"))
    )
    (net (code "101") (name "unconnected-(U$3-D8-PadP$19)") (class "Default")
      (node (ref "U$3") (pin "P$19") (pinfunction "D8_P$19") (pintype "bidirectional"))
    )
    (net (code "102") (name "unconnected-(U$3-D9-PadP$20)") (class "Default")
      (node (ref "U$3") (pin "P$20") (pinfunction "D9_P$20") (pintype "bidirectional"))
    )
    (net (code "103") (name "unconnected-(U$3-D10-PadP$21)") (class "Default")
      (node (ref "U$3") (pin "P$21") (pinfunction "D10_P$21") (pintype "bidirectional"))
    )
    (net (code "104") (name "unconnected-(U$3-D11-PadP$22)") (class "Default")
      (node (ref "U$3") (pin "P$22") (pinfunction "D11_P$22") (pintype "bidirectional"))
    )
    (net (code "105") (name "unconnected-(U$3-D12-PadP$23)") (class "Default")
      (node (ref "U$3") (pin "P$23") (pinfunction "D12_P$23") (pintype "bidirectional"))
    )
    (net (code "106") (name "unconnected-(U$3-D13-PadP$24)") (class "Default")
      (node (ref "U$3") (pin "P$24") (pinfunction "D13_P$24") (pintype "bidirectional"))
    )
    (net (code "107") (name "unconnected-(U$3-D14{slash}TX3-PadP$25)") (class "Default")
      (node (ref "U$3") (pin "P$25") (pinfunction "D14/TX3_P$25") (pintype "bidirectional"))
    )
    (net (code "108") (name "unconnected-(U$3-D15{slash}RX3-PadP$26)") (class "Default")
      (node (ref "U$3") (pin "P$26") (pinfunction "D15/RX3_P$26") (pintype "bidirectional"))
    )
    (net (code "109") (name "unconnected-(U$3-D22-PadP$33)") (class "Default")
      (node (ref "U$3") (pin "P$33") (pinfunction "D22_P$33") (pintype "bidirectional"))
    )
    (net (code "110") (name "unconnected-(U$3-D23-PadP$34)") (class "Default")
      (node (ref "U$3") (pin "P$34") (pinfunction "D23_P$34") (pintype "bidirectional"))
    )
    (net (code "111") (name "unconnected-(U$3-D24-PadP$35)") (class "Default")
      (node (ref "U$3") (pin "P$35") (pinfunction "D24_P$35") (pintype "bidirectional"))
    )
    (net (code "112") (name "unconnected-(U$3-D25-PadP$36)") (class "Default")
      (node (ref "U$3") (pin "P$36") (pinfunction "D25_P$36") (pintype "bidirectional"))
    )
    (net (code "113") (name "unconnected-(U$3-D26-PadP$37)") (class "Default")
      (node (ref "U$3") (pin "P$37") (pinfunction "D26_P$37") (pintype "bidirectional"))
    )
    (net (code "114") (name "unconnected-(U$3-D27-PadP$38)") (class "Default")
      (node (ref "U$3") (pin "P$38") (pinfunction "D27_P$38") (pintype "bidirectional"))
    )
    (net (code "115") (name "unconnected-(U$3-D28-PadP$39)") (class "Default")
      (node (ref "U$3") (pin "P$39") (pinfunction "D28_P$39") (pintype "bidirectional"))
    )
    (net (code "116") (name "unconnected-(U$3-D29-PadP$40)") (class "Default")
      (node (ref "U$3") (pin "P$40") (pinfunction "D29_P$40") (pintype "bidirectional"))
    )
    (net (code "117") (name "unconnected-(U$3-D30-PadP$41)") (class "Default")
      (node (ref "U$3") (pin "P$41") (pinfunction "D30_P$41") (pintype "bidirectional"))
    )
    (net (code "118") (name "unconnected-(U$3-D31-PadP$42)") (class "Default")
      (node (ref "U$3") (pin "P$42") (pinfunction "D31_P$42") (pintype "bidirectional"))
    )
    (net (code "119") (name "unconnected-(U$3-D32-PadP$59)") (class "Default")
      (node (ref "U$3") (pin "P$59") (pinfunction "D32_P$59") (pintype "bidirectional"))
    )
    (net (code "120") (name "unconnected-(U$3-D33-PadP$60)") (class "Default")
      (node (ref "U$3") (pin "P$60") (pinfunction "D33_P$60") (pintype "bidirectional"))
    )
    (net (code "121") (name "unconnected-(U$3-D38-PadP$65)") (class "Default")
      (node (ref "U$3") (pin "P$65") (pinfunction "D38_P$65") (pintype "bidirectional"))
    )
    (net (code "122") (name "unconnected-(U$3-D39-PadP$66)") (class "Default")
      (node (ref "U$3") (pin "P$66") (pinfunction "D39_P$66") (pintype "bidirectional"))
    )
    (net (code "123") (name "unconnected-(U$3-D41-PadP$68)") (class "Default")
      (node (ref "U$3") (pin "P$68") (pinfunction "D41_P$68") (pintype "bidirectional"))
    )
    (net (code "124") (name "unconnected-(U$3-D43-PadP$70)") (class "Default")
      (node (ref "U$3") (pin "P$70") (pinfunction "D43_P$70") (pintype "bidirectional"))
    )
    (net (code "125") (name "unconnected-(U$3-D45-PadP$72)") (class "Default")
      (node (ref "U$3") (pin "P$72") (pinfunction "D45_P$72") (pintype "bidirectional"))
    )
    (net (code "126") (name "unconnected-(U$3-D46-PadP$73)") (class "Default")
      (node (ref "U$3") (pin "P$73") (pinfunction "D46_P$73") (pintype "bidirectional"))
    )
    (net (code "127") (name "unconnected-(U$3-D47-PadP$74)") (class "Default")
      (node (ref "U$3") (pin "P$74") (pinfunction "D47_P$74") (pintype "bidirectional"))
    )
    (net (code "128") (name "unconnected-(U$3-D48-PadP$75)") (class "Default")
      (node (ref "U$3") (pin "P$75") (pinfunction "D48_P$75") (pintype "bidirectional"))
    )
    (net (code "129") (name "unconnected-(U$3-D49-PadP$76)") (class "Default")
      (node (ref "U$3") (pin "P$76") (pinfunction "D49_P$76") (pintype "bidirectional"))
    )
    (net (code "130") (name "unconnected-(U$3-D50{slash}MISO-PadP$77)") (class "Default")
      (node (ref "U$3") (pin "P$77") (pinfunction "D50/MISO_P$77") (pintype "bidirectional"))
    )
    (net (code "131") (name "unconnected-(U$3-D51{slash}MOSI-PadP$78)") (class "Default")
      (node (ref "U$3") (pin "P$78") (pinfunction "D51/MOSI_P$78") (pintype "bidirectional"))
    )
    (net (code "132") (name "unconnected-(U$3-D52{slash}SCK-PadP$79)") (class "Default")
      (node (ref "U$3") (pin "P$79") (pinfunction "D52/SCK_P$79") (pintype "bidirectional"))
    )
    (net (code "133") (name "unconnected-(U$3-D53{slash}SS-PadP$80)") (class "Default")
      (node (ref "U$3") (pin "P$80") (pinfunction "D53/SS_P$80") (pintype "bidirectional"))
    )
    (net (code "134") (name "unconnected-(U$3-PadP$81)") (class "Default")
      (node (ref "U$3") (pin "P$81") (pinfunction "P$81_P$81") (pintype "bidirectional"))
    )
    (net (code "135") (name "unconnected-(U$3-PadP$82)") (class "Default")
      (node (ref "U$3") (pin "P$82") (pinfunction "P$82_P$82") (pintype "bidirectional"))
    )
    (net (code "136") (name "unconnected-(U$3-PadP$83)") (class "Default")
      (node (ref "U$3") (pin "P$83") (pinfunction "P$83_P$83") (pintype "bidirectional"))
    )
    (net (code "137") (name "unconnected-(U$3-PadP$84)") (class "Default")
      (node (ref "U$3") (pin "P$84") (pinfunction "P$84_P$84") (pintype "bidirectional"))
    )
    (net (code "138") (name "unconnected-(U$3-PadP$85)") (class "Default")
      (node (ref "U$3") (pin "P$85") (pinfunction "P$85_P$85") (pintype "bidirectional"))
    )
    (net (code "139") (name "unconnected-(U$3-PadP$86)") (class "Default")
      (node (ref "U$3") (pin "P$86") (pinfunction "P$86_P$86") (pintype "bidirectional"))
    )
    (net (code "140") (name "unconnected-(U$3-RST-PadP$10)") (class "Default")
      (node (ref "U$3") (pin "P$10") (pinfunction "RST_P$10") (pintype "bidirectional"))
    )
    (net (code "141") (name "unconnected-(U$3-RX-PadP$11)") (class "Default")
      (node (ref "U$3") (pin "P$11") (pinfunction "RX_P$11") (pintype "bidirectional"))
    )
    (net (code "142") (name "unconnected-(U$3-TX-PadP$12)") (class "Default")
      (node (ref "U$3") (pin "P$12") (pinfunction "TX_P$12") (pintype "bidirectional"))
    )
    (net (code "143") (name "unconnected-(U$3-VIN1-PadP$1)") (class "Default")
      (node (ref "U$3") (pin "P$1") (pinfunction "VIN1_P$1") (pintype "bidirectional"))
    )
    (net (code "144") (name "unconnected-(U$3-VIN2-PadP$2)") (class "Default")
      (node (ref "U$3") (pin "P$2") (pinfunction "VIN2_P$2") (pintype "bidirectional"))
    )
  )
)
